# charliewatch-norf.net
KiCad netlist of a schematic drawn in EAGLE
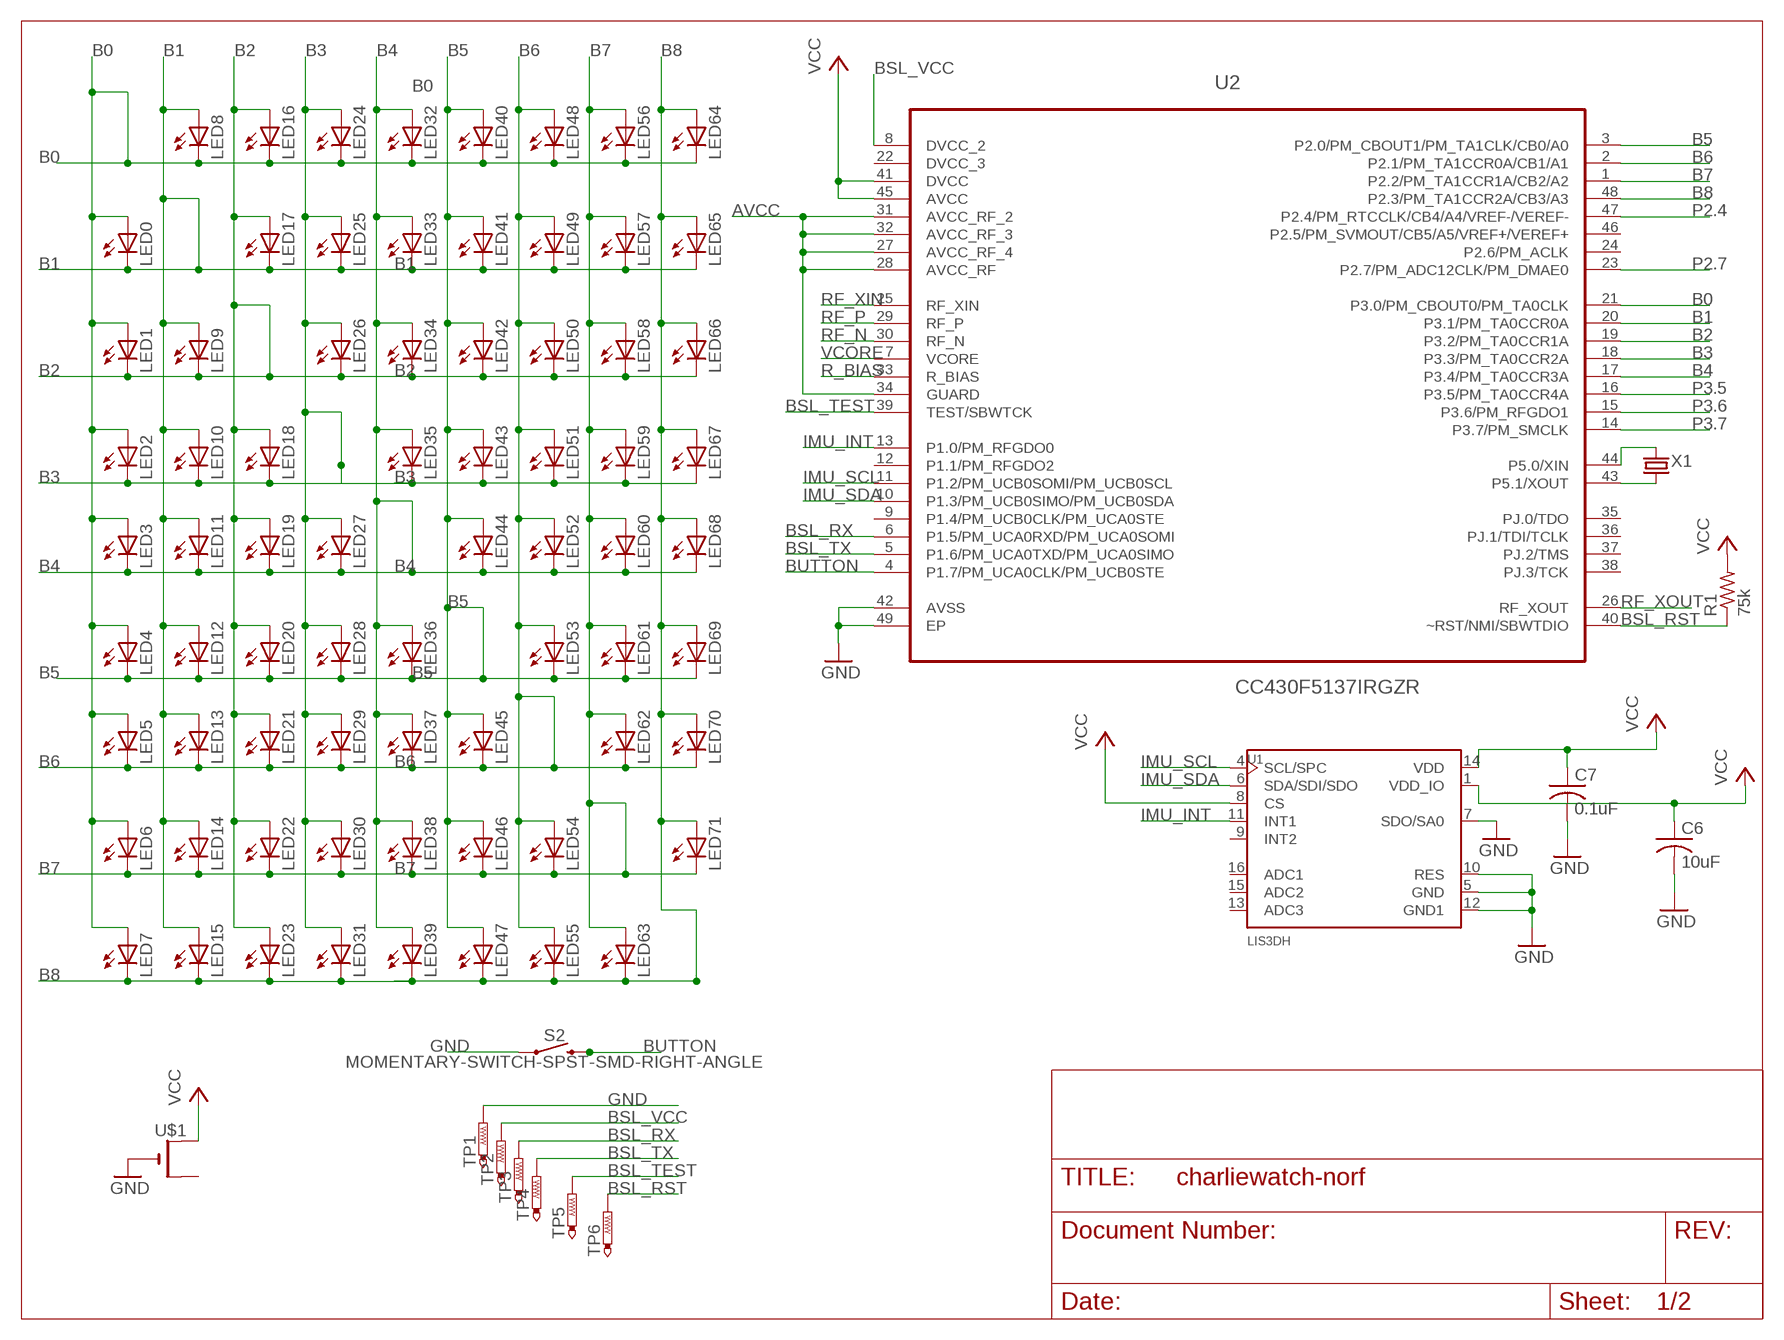
[diagram p0: schematic, sheet 1]

(export (version "E")
  (design (tool "Eeschema 10.0.6"))
  (components
    (comp (ref "C6")
      (value "10uF")
      (footprint "eagle-import:C0603")
      (libsource (lib "eagle-import") (part "C-USC0603"))
    )
    (comp (ref "C7")
      (value "0.1uF")
      (footprint "eagle-import:C0603")
      (libsource (lib "eagle-import") (part "C-USC0603"))
    )
    (comp (ref "LED0")
      (value "LEDCHIPLED_0603")
      (footprint "eagle-import:CHIPLED_0603")
      (libsource (lib "eagle-import") (part "LEDCHIPLED_0603"))
    )
    (comp (ref "LED1")
      (value "LEDCHIPLED_0603")
      (footprint "eagle-import:CHIPLED_0603")
      (libsource (lib "eagle-import") (part "LEDCHIPLED_0603"))
    )
    (comp (ref "LED2")
      (value "LEDCHIPLED_0603")
      (footprint "eagle-import:CHIPLED_0603")
      (libsource (lib "eagle-import") (part "LEDCHIPLED_0603"))
    )
    (comp (ref "LED3")
      (value "LEDCHIPLED_0603")
      (footprint "eagle-import:CHIPLED_0603")
      (libsource (lib "eagle-import") (part "LEDCHIPLED_0603"))
    )
    (comp (ref "LED4")
      (value "LEDCHIPLED_0603")
      (footprint "eagle-import:CHIPLED_0603")
      (libsource (lib "eagle-import") (part "LEDCHIPLED_0603"))
    )
    (comp (ref "LED5")
      (value "LEDCHIPLED_0603")
      (footprint "eagle-import:CHIPLED_0603")
      (libsource (lib "eagle-import") (part "LEDCHIPLED_0603"))
    )
    (comp (ref "LED6")
      (value "LEDCHIPLED_0603")
      (footprint "eagle-import:CHIPLED_0603")
      (libsource (lib "eagle-import") (part "LEDCHIPLED_0603"))
    )
    (comp (ref "LED7")
      (value "LEDCHIPLED_0603")
      (footprint "eagle-import:CHIPLED_0603")
      (libsource (lib "eagle-import") (part "LEDCHIPLED_0603"))
    )
    (comp (ref "LED8")
      (value "LEDCHIPLED_0603")
      (footprint "eagle-import:CHIPLED_0603")
      (libsource (lib "eagle-import") (part "LEDCHIPLED_0603"))
    )
    (comp (ref "LED9")
      (value "LEDCHIPLED_0603")
      (footprint "eagle-import:CHIPLED_0603")
      (libsource (lib "eagle-import") (part "LEDCHIPLED_0603"))
    )
    (comp (ref "LED10")
      (value "LEDCHIPLED_0603")
      (footprint "eagle-import:CHIPLED_0603")
      (libsource (lib "eagle-import") (part "LEDCHIPLED_0603"))
    )
    (comp (ref "LED11")
      (value "LEDCHIPLED_0603")
      (footprint "eagle-import:CHIPLED_0603")
      (libsource (lib "eagle-import") (part "LEDCHIPLED_0603"))
    )
    (comp (ref "LED12")
      (value "LEDCHIPLED_0603")
      (footprint "eagle-import:CHIPLED_0603")
      (libsource (lib "eagle-import") (part "LEDCHIPLED_0603"))
    )
    (comp (ref "LED13")
      (value "LEDCHIPLED_0603")
      (footprint "eagle-import:CHIPLED_0603")
      (libsource (lib "eagle-import") (part "LEDCHIPLED_0603"))
    )
    (comp (ref "LED14")
      (value "LEDCHIPLED_0603")
      (footprint "eagle-import:CHIPLED_0603")
      (libsource (lib "eagle-import") (part "LEDCHIPLED_0603"))
    )
    (comp (ref "LED15")
      (value "LEDCHIPLED_0603")
      (footprint "eagle-import:CHIPLED_0603")
      (libsource (lib "eagle-import") (part "LEDCHIPLED_0603"))
    )
    (comp (ref "LED16")
      (value "LEDCHIPLED_0603")
      (footprint "eagle-import:CHIPLED_0603")
      (libsource (lib "eagle-import") (part "LEDCHIPLED_0603"))
    )
    (comp (ref "LED17")
      (value "LEDCHIPLED_0603")
      (footprint "eagle-import:CHIPLED_0603")
      (libsource (lib "eagle-import") (part "LEDCHIPLED_0603"))
    )
    (comp (ref "LED18")
      (value "LEDCHIPLED_0603")
      (footprint "eagle-import:CHIPLED_0603")
      (libsource (lib "eagle-import") (part "LEDCHIPLED_0603"))
    )
    (comp (ref "LED19")
      (value "LEDCHIPLED_0603")
      (footprint "eagle-import:CHIPLED_0603")
      (libsource (lib "eagle-import") (part "LEDCHIPLED_0603"))
    )
    (comp (ref "LED20")
      (value "LEDCHIPLED_0603")
      (footprint "eagle-import:CHIPLED_0603")
      (libsource (lib "eagle-import") (part "LEDCHIPLED_0603"))
    )
    (comp (ref "LED21")
      (value "LEDCHIPLED_0603")
      (footprint "eagle-import:CHIPLED_0603")
      (libsource (lib "eagle-import") (part "LEDCHIPLED_0603"))
    )
    (comp (ref "LED22")
      (value "LEDCHIPLED_0603")
      (footprint "eagle-import:CHIPLED_0603")
      (libsource (lib "eagle-import") (part "LEDCHIPLED_0603"))
    )
    (comp (ref "LED23")
      (value "LEDCHIPLED_0603")
      (footprint "eagle-import:CHIPLED_0603")
      (libsource (lib "eagle-import") (part "LEDCHIPLED_0603"))
    )
    (comp (ref "LED24")
      (value "LEDCHIPLED_0603")
      (footprint "eagle-import:CHIPLED_0603")
      (libsource (lib "eagle-import") (part "LEDCHIPLED_0603"))
    )
    (comp (ref "LED25")
      (value "LEDCHIPLED_0603")
      (footprint "eagle-import:CHIPLED_0603")
      (libsource (lib "eagle-import") (part "LEDCHIPLED_0603"))
    )
    (comp (ref "LED26")
      (value "LEDCHIPLED_0603")
      (footprint "eagle-import:CHIPLED_0603")
      (libsource (lib "eagle-import") (part "LEDCHIPLED_0603"))
    )
    (comp (ref "LED27")
      (value "LEDCHIPLED_0603")
      (footprint "eagle-import:CHIPLED_0603")
      (libsource (lib "eagle-import") (part "LEDCHIPLED_0603"))
    )
    (comp (ref "LED28")
      (value "LEDCHIPLED_0603")
      (footprint "eagle-import:CHIPLED_0603")
      (libsource (lib "eagle-import") (part "LEDCHIPLED_0603"))
    )
    (comp (ref "LED29")
      (value "LEDCHIPLED_0603")
      (footprint "eagle-import:CHIPLED_0603")
      (libsource (lib "eagle-import") (part "LEDCHIPLED_0603"))
    )
    (comp (ref "LED30")
      (value "LEDCHIPLED_0603")
      (footprint "eagle-import:CHIPLED_0603")
      (libsource (lib "eagle-import") (part "LEDCHIPLED_0603"))
    )
    (comp (ref "LED31")
      (value "LEDCHIPLED_0603")
      (footprint "eagle-import:CHIPLED_0603")
      (libsource (lib "eagle-import") (part "LEDCHIPLED_0603"))
    )
    (comp (ref "LED32")
      (value "LEDCHIPLED_0603")
      (footprint "eagle-import:CHIPLED_0603")
      (libsource (lib "eagle-import") (part "LEDCHIPLED_0603"))
    )
    (comp (ref "LED33")
      (value "LEDCHIPLED_0603")
      (footprint "eagle-import:CHIPLED_0603")
      (libsource (lib "eagle-import") (part "LEDCHIPLED_0603"))
    )
    (comp (ref "LED34")
      (value "LEDCHIPLED_0603")
      (footprint "eagle-import:CHIPLED_0603")
      (libsource (lib "eagle-import") (part "LEDCHIPLED_0603"))
    )
    (comp (ref "LED35")
      (value "LEDCHIPLED_0603")
      (footprint "eagle-import:CHIPLED_0603")
      (libsource (lib "eagle-import") (part "LEDCHIPLED_0603"))
    )
    (comp (ref "LED36")
      (value "LEDCHIPLED_0603")
      (footprint "eagle-import:CHIPLED_0603")
      (libsource (lib "eagle-import") (part "LEDCHIPLED_0603"))
    )
    (comp (ref "LED37")
      (value "LEDCHIPLED_0603")
      (footprint "eagle-import:CHIPLED_0603")
      (libsource (lib "eagle-import") (part "LEDCHIPLED_0603"))
    )
    (comp (ref "LED38")
      (value "LEDCHIPLED_0603")
      (footprint "eagle-import:CHIPLED_0603")
      (libsource (lib "eagle-import") (part "LEDCHIPLED_0603"))
    )
    (comp (ref "LED39")
      (value "LEDCHIPLED_0603")
      (footprint "eagle-import:CHIPLED_0603")
      (libsource (lib "eagle-import") (part "LEDCHIPLED_0603"))
    )
    (comp (ref "LED40")
      (value "LEDCHIPLED_0603")
      (footprint "eagle-import:CHIPLED_0603")
      (libsource (lib "eagle-import") (part "LEDCHIPLED_0603"))
    )
    (comp (ref "LED41")
      (value "LEDCHIPLED_0603")
      (footprint "eagle-import:CHIPLED_0603")
      (libsource (lib "eagle-import") (part "LEDCHIPLED_0603"))
    )
    (comp (ref "LED42")
      (value "LEDCHIPLED_0603")
      (footprint "eagle-import:CHIPLED_0603")
      (libsource (lib "eagle-import") (part "LEDCHIPLED_0603"))
    )
    (comp (ref "LED43")
      (value "LEDCHIPLED_0603")
      (footprint "eagle-import:CHIPLED_0603")
      (libsource (lib "eagle-import") (part "LEDCHIPLED_0603"))
    )
    (comp (ref "LED44")
      (value "LEDCHIPLED_0603")
      (footprint "eagle-import:CHIPLED_0603")
      (libsource (lib "eagle-import") (part "LEDCHIPLED_0603"))
    )
    (comp (ref "LED45")
      (value "LEDCHIPLED_0603")
      (footprint "eagle-import:CHIPLED_0603")
      (libsource (lib "eagle-import") (part "LEDCHIPLED_0603"))
    )
    (comp (ref "LED46")
      (value "LEDCHIPLED_0603")
      (footprint "eagle-import:CHIPLED_0603")
      (libsource (lib "eagle-import") (part "LEDCHIPLED_0603"))
    )
    (comp (ref "LED47")
      (value "LEDCHIPLED_0603")
      (footprint "eagle-import:CHIPLED_0603")
      (libsource (lib "eagle-import") (part "LEDCHIPLED_0603"))
    )
    (comp (ref "LED48")
      (value "LEDCHIPLED_0603")
      (footprint "eagle-import:CHIPLED_0603")
      (libsource (lib "eagle-import") (part "LEDCHIPLED_0603"))
    )
    (comp (ref "LED49")
      (value "LEDCHIPLED_0603")
      (footprint "eagle-import:CHIPLED_0603")
      (libsource (lib "eagle-import") (part "LEDCHIPLED_0603"))
    )
    (comp (ref "LED50")
      (value "LEDCHIPLED_0603")
      (footprint "eagle-import:CHIPLED_0603")
      (libsource (lib "eagle-import") (part "LEDCHIPLED_0603"))
    )
    (comp (ref "LED51")
      (value "LEDCHIPLED_0603")
      (footprint "eagle-import:CHIPLED_0603")
      (libsource (lib "eagle-import") (part "LEDCHIPLED_0603"))
    )
    (comp (ref "LED52")
      (value "LEDCHIPLED_0603")
      (footprint "eagle-import:CHIPLED_0603")
      (libsource (lib "eagle-import") (part "LEDCHIPLED_0603"))
    )
    (comp (ref "LED53")
      (value "LEDCHIPLED_0603")
      (footprint "eagle-import:CHIPLED_0603")
      (libsource (lib "eagle-import") (part "LEDCHIPLED_0603"))
    )
    (comp (ref "LED54")
      (value "LEDCHIPLED_0603")
      (footprint "eagle-import:CHIPLED_0603")
      (libsource (lib "eagle-import") (part "LEDCHIPLED_0603"))
    )
    (comp (ref "LED55")
      (value "LEDCHIPLED_0603")
      (footprint "eagle-import:CHIPLED_0603")
      (libsource (lib "eagle-import") (part "LEDCHIPLED_0603"))
    )
    (comp (ref "LED56")
      (value "LEDCHIPLED_0603")
      (footprint "eagle-import:CHIPLED_0603")
      (libsource (lib "eagle-import") (part "LEDCHIPLED_0603"))
    )
    (comp (ref "LED57")
      (value "LEDCHIPLED_0603")
      (footprint "eagle-import:CHIPLED_0603")
      (libsource (lib "eagle-import") (part "LEDCHIPLED_0603"))
    )
    (comp (ref "LED58")
      (value "LEDCHIPLED_0603")
      (footprint "eagle-import:CHIPLED_0603")
      (libsource (lib "eagle-import") (part "LEDCHIPLED_0603"))
    )
    (comp (ref "LED59")
      (value "LEDCHIPLED_0603")
      (footprint "eagle-import:CHIPLED_0603")
      (libsource (lib "eagle-import") (part "LEDCHIPLED_0603"))
    )
    (comp (ref "LED60")
      (value "LEDCHIPLED_0603")
      (footprint "eagle-import:CHIPLED_0603")
      (libsource (lib "eagle-import") (part "LEDCHIPLED_0603"))
    )
    (comp (ref "LED61")
      (value "LEDCHIPLED_0603")
      (footprint "eagle-import:CHIPLED_0603")
      (libsource (lib "eagle-import") (part "LEDCHIPLED_0603"))
    )
    (comp (ref "LED62")
      (value "LEDCHIPLED_0603")
      (footprint "eagle-import:CHIPLED_0603")
      (libsource (lib "eagle-import") (part "LEDCHIPLED_0603"))
    )
    (comp (ref "LED63")
      (value "LEDCHIPLED_0603")
      (footprint "eagle-import:CHIPLED_0603")
      (libsource (lib "eagle-import") (part "LEDCHIPLED_0603"))
    )
    (comp (ref "LED64")
      (value "LEDCHIPLED_0603")
      (footprint "eagle-import:CHIPLED_0603")
      (libsource (lib "eagle-import") (part "LEDCHIPLED_0603"))
    )
    (comp (ref "LED65")
      (value "LEDCHIPLED_0603")
      (footprint "eagle-import:CHIPLED_0603")
      (libsource (lib "eagle-import") (part "LEDCHIPLED_0603"))
    )
    (comp (ref "LED66")
      (value "LEDCHIPLED_0603")
      (footprint "eagle-import:CHIPLED_0603")
      (libsource (lib "eagle-import") (part "LEDCHIPLED_0603"))
    )
    (comp (ref "LED67")
      (value "LEDCHIPLED_0603")
      (footprint "eagle-import:CHIPLED_0603")
      (libsource (lib "eagle-import") (part "LEDCHIPLED_0603"))
    )
    (comp (ref "LED68")
      (value "LEDCHIPLED_0603")
      (footprint "eagle-import:CHIPLED_0603")
      (libsource (lib "eagle-import") (part "LEDCHIPLED_0603"))
    )
    (comp (ref "LED69")
      (value "LEDCHIPLED_0603")
      (footprint "eagle-import:CHIPLED_0603")
      (libsource (lib "eagle-import") (part "LEDCHIPLED_0603"))
    )
    (comp (ref "LED70")
      (value "LEDCHIPLED_0603")
      (footprint "eagle-import:CHIPLED_0603")
      (libsource (lib "eagle-import") (part "LEDCHIPLED_0603"))
    )
    (comp (ref "LED71")
      (value "LEDCHIPLED_0603")
      (footprint "eagle-import:CHIPLED_0603")
      (libsource (lib "eagle-import") (part "LEDCHIPLED_0603"))
    )
    (comp (ref "R1")
      (value "75k")
      (footprint "eagle-import:R0402")
      (libsource (lib "eagle-import") (part "R-US_R0402"))
    )
    (comp (ref "S2")
      (value "MOMENTARY-SWITCH-SPST-SMD-RIGHT-ANGLE")
      (footprint "eagle-import:TACTILE_SWITCH_SMD_RIGHT_ANGLE")
      (libsource (lib "eagle-import") (part "MOMENTARY-SWITCH-SPST-SMD-RIGHT-ANGLE"))
    )
    (comp (ref "TP1")
      (value "PTR1TP10SQ")
      (footprint "eagle-import:TP10SQ")
      (libsource (lib "eagle-import") (part "PTR1TP10SQ"))
    )
    (comp (ref "TP2")
      (value "PTR1TP10R")
      (footprint "eagle-import:TP10R")
      (libsource (lib "eagle-import") (part "PTR1TP10R"))
    )
    (comp (ref "TP3")
      (value "PTR1TP10R")
      (footprint "eagle-import:TP10R")
      (libsource (lib "eagle-import") (part "PTR1TP10R"))
    )
    (comp (ref "TP4")
      (value "PTR1TP10R")
      (footprint "eagle-import:TP10R")
      (libsource (lib "eagle-import") (part "PTR1TP10R"))
    )
    (comp (ref "TP5")
      (value "PTR1TP10R")
      (footprint "eagle-import:TP10R")
      (libsource (lib "eagle-import") (part "PTR1TP10R"))
    )
    (comp (ref "TP6")
      (value "PTR1TP10R")
      (footprint "eagle-import:TP10R")
      (libsource (lib "eagle-import") (part "PTR1TP10R"))
    )
    (comp (ref "U$1")
      (value "CR2032SMT")
      (footprint "eagle-import:CR2032-SMD")
      (libsource (lib "eagle-import") (part "CR2032SMT"))
    )
    (comp (ref "U1")
      (value "LIS3DH")
      (footprint "eagle-import:PQFN50P300X300X100-16N")
      (fields (field (name "MF") "STMicroelectronics"))
      (libsource (lib "eagle-import") (part "LIS3DH"))
    )
    (comp (ref "U2")
      (value "CC430F5137IRGZR")
      (footprint "eagle-import:QFN50P700X700X100-49N")
      (libsource (lib "eagle-import") (part "CC430F5137IRGZR"))
    )
    (comp (ref "X1")
      (value "CRYSTALS-NOGND-IQXC-25")
      (footprint "eagle-import:2.0X1.2-2PAD")
      (libsource (lib "eagle-import") (part "CRYSTALS-NOGND-IQXC-25"))
    )
  )
  (nets
    (net (code "1") (name "AVCC") (class "Default")
      (node (ref "U2") (pin "27") (pinfunction "AVCC_RF_4_27") (pintype "power_in"))
      (node (ref "U2") (pin "28") (pinfunction "AVCC_RF_28") (pintype "power_in"))
      (node (ref "U2") (pin "31") (pinfunction "AVCC_RF_2_31") (pintype "power_in"))
      (node (ref "U2") (pin "32") (pinfunction "AVCC_RF_3_32") (pintype "power_in"))
      (node (ref "U2") (pin "34") (pinfunction "GUARD_34") (pintype "input"))
    )
    (net (code "2") (name "B0") (class "Default")
      (node (ref "LED0") (pin "A") (pinfunction "A_A") (pintype "passive"))
      (node (ref "LED1") (pin "A") (pinfunction "A_A") (pintype "passive"))
      (node (ref "LED16") (pin "C") (pinfunction "C_C") (pintype "passive"))
      (node (ref "LED2") (pin "A") (pinfunction "A_A") (pintype "passive"))
      (node (ref "LED24") (pin "C") (pinfunction "C_C") (pintype "passive"))
      (node (ref "LED3") (pin "A") (pinfunction "A_A") (pintype "passive"))
      (node (ref "LED32") (pin "C") (pinfunction "C_C") (pintype "passive"))
      (node (ref "LED4") (pin "A") (pinfunction "A_A") (pintype "passive"))
      (node (ref "LED40") (pin "C") (pinfunction "C_C") (pintype "passive"))
      (node (ref "LED48") (pin "C") (pinfunction "C_C") (pintype "passive"))
      (node (ref "LED5") (pin "A") (pinfunction "A_A") (pintype "passive"))
      (node (ref "LED56") (pin "C") (pinfunction "C_C") (pintype "passive"))
      (node (ref "LED6") (pin "A") (pinfunction "A_A") (pintype "passive"))
      (node (ref "LED64") (pin "C") (pinfunction "C_C") (pintype "passive"))
      (node (ref "LED7") (pin "A") (pinfunction "A_A") (pintype "passive"))
      (node (ref "LED8") (pin "C") (pinfunction "C_C") (pintype "passive"))
      (node (ref "U2") (pin "21") (pinfunction "P3.0/PM_CBOUT0/PM_TA0CLK_21") (pintype "bidirectional"))
    )
    (net (code "3") (name "B1") (class "Default")
      (node (ref "LED0") (pin "C") (pinfunction "C_C") (pintype "passive"))
      (node (ref "LED10") (pin "A") (pinfunction "A_A") (pintype "passive"))
      (node (ref "LED11") (pin "A") (pinfunction "A_A") (pintype "passive"))
      (node (ref "LED12") (pin "A") (pinfunction "A_A") (pintype "passive"))
      (node (ref "LED13") (pin "A") (pinfunction "A_A") (pintype "passive"))
      (node (ref "LED14") (pin "A") (pinfunction "A_A") (pintype "passive"))
      (node (ref "LED15") (pin "A") (pinfunction "A_A") (pintype "passive"))
      (node (ref "LED17") (pin "C") (pinfunction "C_C") (pintype "passive"))
      (node (ref "LED25") (pin "C") (pinfunction "C_C") (pintype "passive"))
      (node (ref "LED33") (pin "C") (pinfunction "C_C") (pintype "passive"))
      (node (ref "LED41") (pin "C") (pinfunction "C_C") (pintype "passive"))
      (node (ref "LED49") (pin "C") (pinfunction "C_C") (pintype "passive"))
      (node (ref "LED57") (pin "C") (pinfunction "C_C") (pintype "passive"))
      (node (ref "LED65") (pin "C") (pinfunction "C_C") (pintype "passive"))
      (node (ref "LED8") (pin "A") (pinfunction "A_A") (pintype "passive"))
      (node (ref "LED9") (pin "A") (pinfunction "A_A") (pintype "passive"))
      (node (ref "U2") (pin "20") (pinfunction "P3.1/PM_TA0CCR0A_20") (pintype "bidirectional"))
    )
    (net (code "4") (name "B2") (class "Default")
      (node (ref "LED1") (pin "C") (pinfunction "C_C") (pintype "passive"))
      (node (ref "LED16") (pin "A") (pinfunction "A_A") (pintype "passive"))
      (node (ref "LED17") (pin "A") (pinfunction "A_A") (pintype "passive"))
      (node (ref "LED18") (pin "A") (pinfunction "A_A") (pintype "passive"))
      (node (ref "LED19") (pin "A") (pinfunction "A_A") (pintype "passive"))
      (node (ref "LED20") (pin "A") (pinfunction "A_A") (pintype "passive"))
      (node (ref "LED21") (pin "A") (pinfunction "A_A") (pintype "passive"))
      (node (ref "LED22") (pin "A") (pinfunction "A_A") (pintype "passive"))
      (node (ref "LED23") (pin "A") (pinfunction "A_A") (pintype "passive"))
      (node (ref "LED26") (pin "C") (pinfunction "C_C") (pintype "passive"))
      (node (ref "LED34") (pin "C") (pinfunction "C_C") (pintype "passive"))
      (node (ref "LED42") (pin "C") (pinfunction "C_C") (pintype "passive"))
      (node (ref "LED50") (pin "C") (pinfunction "C_C") (pintype "passive"))
      (node (ref "LED58") (pin "C") (pinfunction "C_C") (pintype "passive"))
      (node (ref "LED66") (pin "C") (pinfunction "C_C") (pintype "passive"))
      (node (ref "LED9") (pin "C") (pinfunction "C_C") (pintype "passive"))
      (node (ref "U2") (pin "19") (pinfunction "P3.2/PM_TA0CCR1A_19") (pintype "bidirectional"))
    )
    (net (code "5") (name "B3") (class "Default")
      (node (ref "LED10") (pin "C") (pinfunction "C_C") (pintype "passive"))
      (node (ref "LED18") (pin "C") (pinfunction "C_C") (pintype "passive"))
      (node (ref "LED2") (pin "C") (pinfunction "C_C") (pintype "passive"))
      (node (ref "LED24") (pin "A") (pinfunction "A_A") (pintype "passive"))
      (node (ref "LED25") (pin "A") (pinfunction "A_A") (pintype "passive"))
      (node (ref "LED26") (pin "A") (pinfunction "A_A") (pintype "passive"))
      (node (ref "LED27") (pin "A") (pinfunction "A_A") (pintype "passive"))
      (node (ref "LED28") (pin "A") (pinfunction "A_A") (pintype "passive"))
      (node (ref "LED29") (pin "A") (pinfunction "A_A") (pintype "passive"))
      (node (ref "LED30") (pin "A") (pinfunction "A_A") (pintype "passive"))
      (node (ref "LED31") (pin "A") (pinfunction "A_A") (pintype "passive"))
      (node (ref "LED35") (pin "C") (pinfunction "C_C") (pintype "passive"))
      (node (ref "LED43") (pin "C") (pinfunction "C_C") (pintype "passive"))
      (node (ref "LED51") (pin "C") (pinfunction "C_C") (pintype "passive"))
      (node (ref "LED59") (pin "C") (pinfunction "C_C") (pintype "passive"))
      (node (ref "LED67") (pin "C") (pinfunction "C_C") (pintype "passive"))
      (node (ref "U2") (pin "18") (pinfunction "P3.3/PM_TA0CCR2A_18") (pintype "bidirectional"))
    )
    (net (code "6") (name "B4") (class "Default")
      (node (ref "LED11") (pin "C") (pinfunction "C_C") (pintype "passive"))
      (node (ref "LED19") (pin "C") (pinfunction "C_C") (pintype "passive"))
      (node (ref "LED27") (pin "C") (pinfunction "C_C") (pintype "passive"))
      (node (ref "LED3") (pin "C") (pinfunction "C_C") (pintype "passive"))
      (node (ref "LED32") (pin "A") (pinfunction "A_A") (pintype "passive"))
      (node (ref "LED33") (pin "A") (pinfunction "A_A") (pintype "passive"))
      (node (ref "LED34") (pin "A") (pinfunction "A_A") (pintype "passive"))
      (node (ref "LED35") (pin "A") (pinfunction "A_A") (pintype "passive"))
      (node (ref "LED36") (pin "A") (pinfunction "A_A") (pintype "passive"))
      (node (ref "LED37") (pin "A") (pinfunction "A_A") (pintype "passive"))
      (node (ref "LED38") (pin "A") (pinfunction "A_A") (pintype "passive"))
      (node (ref "LED39") (pin "A") (pinfunction "A_A") (pintype "passive"))
      (node (ref "LED44") (pin "C") (pinfunction "C_C") (pintype "passive"))
      (node (ref "LED52") (pin "C") (pinfunction "C_C") (pintype "passive"))
      (node (ref "LED60") (pin "C") (pinfunction "C_C") (pintype "passive"))
      (node (ref "LED68") (pin "C") (pinfunction "C_C") (pintype "passive"))
      (node (ref "U2") (pin "17") (pinfunction "P3.4/PM_TA0CCR3A_17") (pintype "bidirectional"))
    )
    (net (code "7") (name "B5") (class "Default")
      (node (ref "LED12") (pin "C") (pinfunction "C_C") (pintype "passive"))
      (node (ref "LED20") (pin "C") (pinfunction "C_C") (pintype "passive"))
      (node (ref "LED28") (pin "C") (pinfunction "C_C") (pintype "passive"))
      (node (ref "LED36") (pin "C") (pinfunction "C_C") (pintype "passive"))
      (node (ref "LED4") (pin "C") (pinfunction "C_C") (pintype "passive"))
      (node (ref "LED40") (pin "A") (pinfunction "A_A") (pintype "passive"))
      (node (ref "LED41") (pin "A") (pinfunction "A_A") (pintype "passive"))
      (node (ref "LED42") (pin "A") (pinfunction "A_A") (pintype "passive"))
      (node (ref "LED43") (pin "A") (pinfunction "A_A") (pintype "passive"))
      (node (ref "LED44") (pin "A") (pinfunction "A_A") (pintype "passive"))
      (node (ref "LED45") (pin "A") (pinfunction "A_A") (pintype "passive"))
      (node (ref "LED46") (pin "A") (pinfunction "A_A") (pintype "passive"))
      (node (ref "LED47") (pin "A") (pinfunction "A_A") (pintype "passive"))
      (node (ref "LED53") (pin "C") (pinfunction "C_C") (pintype "passive"))
      (node (ref "LED61") (pin "C") (pinfunction "C_C") (pintype "passive"))
      (node (ref "LED69") (pin "C") (pinfunction "C_C") (pintype "passive"))
      (node (ref "U2") (pin "3") (pinfunction "P2.0/PM_CBOUT1/PM_TA1CLK/CB0/A0_3") (pintype "bidirectional"))
    )
    (net (code "8") (name "B6") (class "Default")
      (node (ref "LED13") (pin "C") (pinfunction "C_C") (pintype "passive"))
      (node (ref "LED21") (pin "C") (pinfunction "C_C") (pintype "passive"))
      (node (ref "LED29") (pin "C") (pinfunction "C_C") (pintype "passive"))
      (node (ref "LED37") (pin "C") (pinfunction "C_C") (pintype "passive"))
      (node (ref "LED45") (pin "C") (pinfunction "C_C") (pintype "passive"))
      (node (ref "LED48") (pin "A") (pinfunction "A_A") (pintype "passive"))
      (node (ref "LED49") (pin "A") (pinfunction "A_A") (pintype "passive"))
      (node (ref "LED5") (pin "C") (pinfunction "C_C") (pintype "passive"))
      (node (ref "LED50") (pin "A") (pinfunction "A_A") (pintype "passive"))
      (node (ref "LED51") (pin "A") (pinfunction "A_A") (pintype "passive"))
      (node (ref "LED52") (pin "A") (pinfunction "A_A") (pintype "passive"))
      (node (ref "LED53") (pin "A") (pinfunction "A_A") (pintype "passive"))
      (node (ref "LED54") (pin "A") (pinfunction "A_A") (pintype "passive"))
      (node (ref "LED55") (pin "A") (pinfunction "A_A") (pintype "passive"))
      (node (ref "LED62") (pin "C") (pinfunction "C_C") (pintype "passive"))
      (node (ref "LED70") (pin "C") (pinfunction "C_C") (pintype "passive"))
      (node (ref "U2") (pin "2") (pinfunction "P2.1/PM_TA1CCR0A/CB1/A1_2") (pintype "bidirectional"))
    )
    (net (code "9") (name "B7") (class "Default")
      (node (ref "LED14") (pin "C") (pinfunction "C_C") (pintype "passive"))
      (node (ref "LED22") (pin "C") (pinfunction "C_C") (pintype "passive"))
      (node (ref "LED30") (pin "C") (pinfunction "C_C") (pintype "passive"))
      (node (ref "LED38") (pin "C") (pinfunction "C_C") (pintype "passive"))
      (node (ref "LED46") (pin "C") (pinfunction "C_C") (pintype "passive"))
      (node (ref "LED54") (pin "C") (pinfunction "C_C") (pintype "passive"))
      (node (ref "LED56") (pin "A") (pinfunction "A_A") (pintype "passive"))
      (node (ref "LED57") (pin "A") (pinfunction "A_A") (pintype "passive"))
      (node (ref "LED58") (pin "A") (pinfunction "A_A") (pintype "passive"))
      (node (ref "LED59") (pin "A") (pinfunction "A_A") (pintype "passive"))
      (node (ref "LED6") (pin "C") (pinfunction "C_C") (pintype "passive"))
      (node (ref "LED60") (pin "A") (pinfunction "A_A") (pintype "passive"))
      (node (ref "LED61") (pin "A") (pinfunction "A_A") (pintype "passive"))
      (node (ref "LED62") (pin "A") (pinfunction "A_A") (pintype "passive"))
      (node (ref "LED63") (pin "A") (pinfunction "A_A") (pintype "passive"))
      (node (ref "LED71") (pin "C") (pinfunction "C_C") (pintype "passive"))
      (node (ref "U2") (pin "1") (pinfunction "P2.2/PM_TA1CCR1A/CB2/A2_1") (pintype "bidirectional"))
    )
    (net (code "10") (name "B8") (class "Default")
      (node (ref "LED15") (pin "C") (pinfunction "C_C") (pintype "passive"))
      (node (ref "LED23") (pin "C") (pinfunction "C_C") (pintype "passive"))
      (node (ref "LED31") (pin "C") (pinfunction "C_C") (pintype "passive"))
      (node (ref "LED39") (pin "C") (pinfunction "C_C") (pintype "passive"))
      (node (ref "LED47") (pin "C") (pinfunction "C_C") (pintype "passive"))
      (node (ref "LED55") (pin "C") (pinfunction "C_C") (pintype "passive"))
      (node (ref "LED63") (pin "C") (pinfunction "C_C") (pintype "passive"))
      (node (ref "LED64") (pin "A") (pinfunction "A_A") (pintype "passive"))
      (node (ref "LED65") (pin "A") (pinfunction "A_A") (pintype "passive"))
      (node (ref "LED66") (pin "A") (pinfunction "A_A") (pintype "passive"))
      (node (ref "LED67") (pin "A") (pinfunction "A_A") (pintype "passive"))
      (node (ref "LED68") (pin "A") (pinfunction "A_A") (pintype "passive"))
      (node (ref "LED69") (pin "A") (pinfunction "A_A") (pintype "passive"))
      (node (ref "LED7") (pin "C") (pinfunction "C_C") (pintype "passive"))
      (node (ref "LED70") (pin "A") (pinfunction "A_A") (pintype "passive"))
      (node (ref "LED71") (pin "A") (pinfunction "A_A") (pintype "passive"))
      (node (ref "U2") (pin "48") (pinfunction "P2.3/PM_TA1CCR2A/CB3/A3_48") (pintype "bidirectional"))
    )
    (net (code "11") (name "BSL_RST") (class "Default")
      (node (ref "R1") (pin "1") (pinfunction "1_1") (pintype "passive"))
      (node (ref "TP6") (pin "TP") (pinfunction "TP_TP") (pintype "input"))
      (node (ref "U2") (pin "40") (pinfunction "~{RST/NMI/SBWTDIO}_40") (pintype "bidirectional"))
    )
    (net (code "12") (name "BSL_RX") (class "Default")
      (node (ref "TP3") (pin "TP") (pinfunction "TP_TP") (pintype "input"))
      (node (ref "U2") (pin "6") (pinfunction "P1.5/PM_UCA0RXD/PM_UCA0SOMI_6") (pintype "bidirectional"))
    )
    (net (code "13") (name "BSL_TEST") (class "Default")
      (node (ref "TP5") (pin "TP") (pinfunction "TP_TP") (pintype "input"))
      (node (ref "U2") (pin "39") (pinfunction "TEST/SBWTCK_39") (pintype "input"))
    )
    (net (code "14") (name "BSL_TX") (class "Default")
      (node (ref "TP4") (pin "TP") (pinfunction "TP_TP") (pintype "input"))
      (node (ref "U2") (pin "5") (pinfunction "P1.6/PM_UCA0TXD/PM_UCA0SIMO_5") (pintype "bidirectional"))
    )
    (net (code "15") (name "BSL_VCC") (class "Default")
      (node (ref "TP2") (pin "TP") (pinfunction "TP_TP") (pintype "input"))
      (node (ref "U2") (pin "8") (pinfunction "DVCC_2_8") (pintype "power_in"))
    )
    (net (code "16") (name "BUTTON") (class "Default")
      (node (ref "S2") (pin "2") (pinfunction "2_2") (pintype "passive"))
      (node (ref "U2") (pin "4") (pinfunction "P1.7/PM_UCA0CLK/PM_UCB0STE_4") (pintype "bidirectional"))
    )
    (net (code "17") (name "DVCC_3") (class "Default")
      (node (ref "U2") (pin "22") (pinfunction "DVCC_3_22") (pintype "power_in"))
    )
    (net (code "18") (name "GND") (class "Default")
      (node (ref "C6") (pin "2") (pinfunction "2_2") (pintype "passive"))
      (node (ref "C7") (pin "2") (pinfunction "2_2") (pintype "passive"))
      (node (ref "S2") (pin "1") (pinfunction "1_1") (pintype "passive"))
      (node (ref "TP1") (pin "TP") (pinfunction "TP_TP") (pintype "input"))
      (node (ref "U$1") (pin "-") (pinfunction "-_-") (pintype "passive"))
      (node (ref "U1") (pin "10") (pinfunction "RES_10") (pintype "power_in"))
      (node (ref "U1") (pin "12") (pinfunction "GND1_12") (pintype "power_in"))
      (node (ref "U1") (pin "5") (pinfunction "GND_5") (pintype "power_in"))
      (node (ref "U1") (pin "7") (pinfunction "SDO/SA0_7") (pintype "output"))
      (node (ref "U2") (pin "42") (pinfunction "AVSS_42") (pintype "passive"))
      (node (ref "U2") (pin "49") (pinfunction "EP_49") (pintype "passive"))
    )
    (net (code "19") (name "IMU_INT") (class "Default")
      (node (ref "U1") (pin "11") (pinfunction "INT1_11") (pintype "input"))
      (node (ref "U2") (pin "13") (pinfunction "P1.0/PM_RFGDO0_13") (pintype "bidirectional"))
    )
    (net (code "20") (name "IMU_SCL") (class "Default")
      (node (ref "U1") (pin "4") (pinfunction "SCL/SPC_4") (pintype "input"))
      (node (ref "U2") (pin "11") (pinfunction "P1.2/PM_UCB0SOMI/PM_UCB0SCL_11") (pintype "bidirectional"))
    )
    (net (code "21") (name "IMU_SDA") (class "Default")
      (node (ref "U1") (pin "6") (pinfunction "SDA/SDI/SDO_6") (pintype "input"))
      (node (ref "U2") (pin "10") (pinfunction "P1.3/PM_UCB0SIMO/PM_UCB0SDA_10") (pintype "bidirectional"))
    )
    (net (code "22") (name "Net-(U2-P5.0{slash}XIN)") (class "Default")
      (node (ref "U2") (pin "44") (pinfunction "P5.0/XIN_44") (pintype "bidirectional"))
      (node (ref "X1") (pin "2") (pinfunction "2_2") (pintype "passive"))
    )
    (net (code "23") (name "Net-(U2-P5.1{slash}XOUT)") (class "Default")
      (node (ref "U2") (pin "43") (pinfunction "P5.1/XOUT_43") (pintype "bidirectional"))
      (node (ref "X1") (pin "1") (pinfunction "1_1") (pintype "passive"))
    )
    (net (code "24") (name "P2.4") (class "Default")
      (node (ref "U2") (pin "47") (pinfunction "P2.4/PM_RTCCLK/CB4/A4/VREF-/VEREF-_47") (pintype "bidirectional"))
    )
    (net (code "25") (name "P2.7") (class "Default")
      (node (ref "U2") (pin "23") (pinfunction "P2.7/PM_ADC12CLK/PM_DMAE0_23") (pintype "bidirectional"))
    )
    (net (code "26") (name "P3.5") (class "Default")
      (node (ref "U2") (pin "16") (pinfunction "P3.5/PM_TA0CCR4A_16") (pintype "bidirectional"))
    )
    (net (code "27") (name "P3.6") (class "Default")
      (node (ref "U2") (pin "15") (pinfunction "P3.6/PM_RFGDO1_15") (pintype "bidirectional"))
    )
    (net (code "28") (name "P3.7") (class "Default")
      (node (ref "U2") (pin "14") (pinfunction "P3.7/PM_SMCLK_14") (pintype "bidirectional"))
    )
    (net (code "29") (name "RF_N") (class "Default")
      (node (ref "U2") (pin "30") (pinfunction "RF_N_30") (pintype "bidirectional"))
    )
    (net (code "30") (name "RF_P") (class "Default")
      (node (ref "U2") (pin "29") (pinfunction "RF_P_29") (pintype "bidirectional"))
    )
    (net (code "31") (name "RF_XIN") (class "Default")
      (node (ref "U2") (pin "25") (pinfunction "RF_XIN_25") (pintype "input"))
    )
    (net (code "32") (name "RF_XOUT") (class "Default")
      (node (ref "U2") (pin "26") (pinfunction "RF_XOUT_26") (pintype "output"))
    )
    (net (code "33") (name "R_BIAS") (class "Default")
      (node (ref "U2") (pin "33") (pinfunction "R_BIAS_33") (pintype "input"))
    )
    (net (code "34") (name "VCC") (class "Default")
      (node (ref "C6") (pin "1") (pinfunction "1_1") (pintype "passive"))
      (node (ref "C7") (pin "1") (pinfunction "1_1") (pintype "passive"))
      (node (ref "R1") (pin "2") (pinfunction "2_2") (pintype "passive"))
      (node (ref "U$1") (pin "+$1") (pinfunction "+_+$1") (pintype "passive"))
      (node (ref "U1") (pin "1") (pinfunction "VDD_IO_1") (pintype "power_in"))
      (node (ref "U1") (pin "14") (pinfunction "VDD_14") (pintype "power_in"))
      (node (ref "U1") (pin "8") (pinfunction "CS_8") (pintype "input"))
      (node (ref "U2") (pin "41") (pinfunction "DVCC_41") (pintype "power_in"))
      (node (ref "U2") (pin "45") (pinfunction "AVCC_45") (pintype "power_in"))
    )
    (net (code "35") (name "VCORE") (class "Default")
      (node (ref "U2") (pin "7") (pinfunction "VCORE_7") (pintype "input"))
    )
    (net (code "36") (name "unconnected-(U$1-+1-Pad+$2)") (class "Default")
      (node (ref "U$1") (pin "+$2") (pinfunction "+1_+$2") (pintype "passive"))
    )
    (net (code "37") (name "unconnected-(U1-ADC1-Pad16)") (class "Default")
      (node (ref "U1") (pin "16") (pinfunction "ADC1_16") (pintype "input"))
    )
    (net (code "38") (name "unconnected-(U1-ADC2-Pad15)") (class "Default")
      (node (ref "U1") (pin "15") (pinfunction "ADC2_15") (pintype "input"))
    )
    (net (code "39") (name "unconnected-(U1-ADC3-Pad13)") (class "Default")
      (node (ref "U1") (pin "13") (pinfunction "ADC3_13") (pintype "input"))
    )
    (net (code "40") (name "unconnected-(U1-INT2-Pad9)") (class "Default")
      (node (ref "U1") (pin "9") (pinfunction "INT2_9") (pintype "input"))
    )
    (net (code "41") (name "unconnected-(U2-P1.1{slash}PM_RFGDO2-Pad12)") (class "Default")
      (node (ref "U2") (pin "12") (pinfunction "P1.1/PM_RFGDO2_12") (pintype "bidirectional"))
    )
    (net (code "42") (name "unconnected-(U2-P1.4{slash}PM_UCB0CLK{slash}PM_UCA0STE-Pad9)") (class "Default")
      (node (ref "U2") (pin "9") (pinfunction "P1.4/PM_UCB0CLK/PM_UCA0STE_9") (pintype "bidirectional"))
    )
    (net (code "43") (name "unconnected-(U2-P2.5{slash}PM_SVMOUT{slash}CB5{slash}A5{slash}VREF+{slash}VEREF+-Pad46)") (class "Default")
      (node (ref "U2") (pin "46") (pinfunction "P2.5/PM_SVMOUT/CB5/A5/VREF+/VEREF+_46") (pintype "bidirectional"))
    )
    (net (code "44") (name "unconnected-(U2-P2.6{slash}PM_ACLK-Pad24)") (class "Default")
      (node (ref "U2") (pin "24") (pinfunction "P2.6/PM_ACLK_24") (pintype "bidirectional"))
    )
    (net (code "45") (name "unconnected-(U2-PJ.0{slash}TDO-Pad35)") (class "Default")
      (node (ref "U2") (pin "35") (pinfunction "PJ.0/TDO_35") (pintype "bidirectional"))
    )
    (net (code "46") (name "unconnected-(U2-PJ.1{slash}TDI{slash}TCLK-Pad36)") (class "Default")
      (node (ref "U2") (pin "36") (pinfunction "PJ.1/TDI/TCLK_36") (pintype "bidirectional"))
    )
    (net (code "47") (name "unconnected-(U2-PJ.2{slash}TMS-Pad37)") (class "Default")
      (node (ref "U2") (pin "37") (pinfunction "PJ.2/TMS_37") (pintype "bidirectional"))
    )
    (net (code "48") (name "unconnected-(U2-PJ.3{slash}TCK-Pad38)") (class "Default")
      (node (ref "U2") (pin "38") (pinfunction "PJ.3/TCK_38") (pintype "bidirectional"))
    )
  )
)
